# SCH_doorbellv2_2026-01-17.net
KiCad netlist of a schematic drawn in EasyEDA
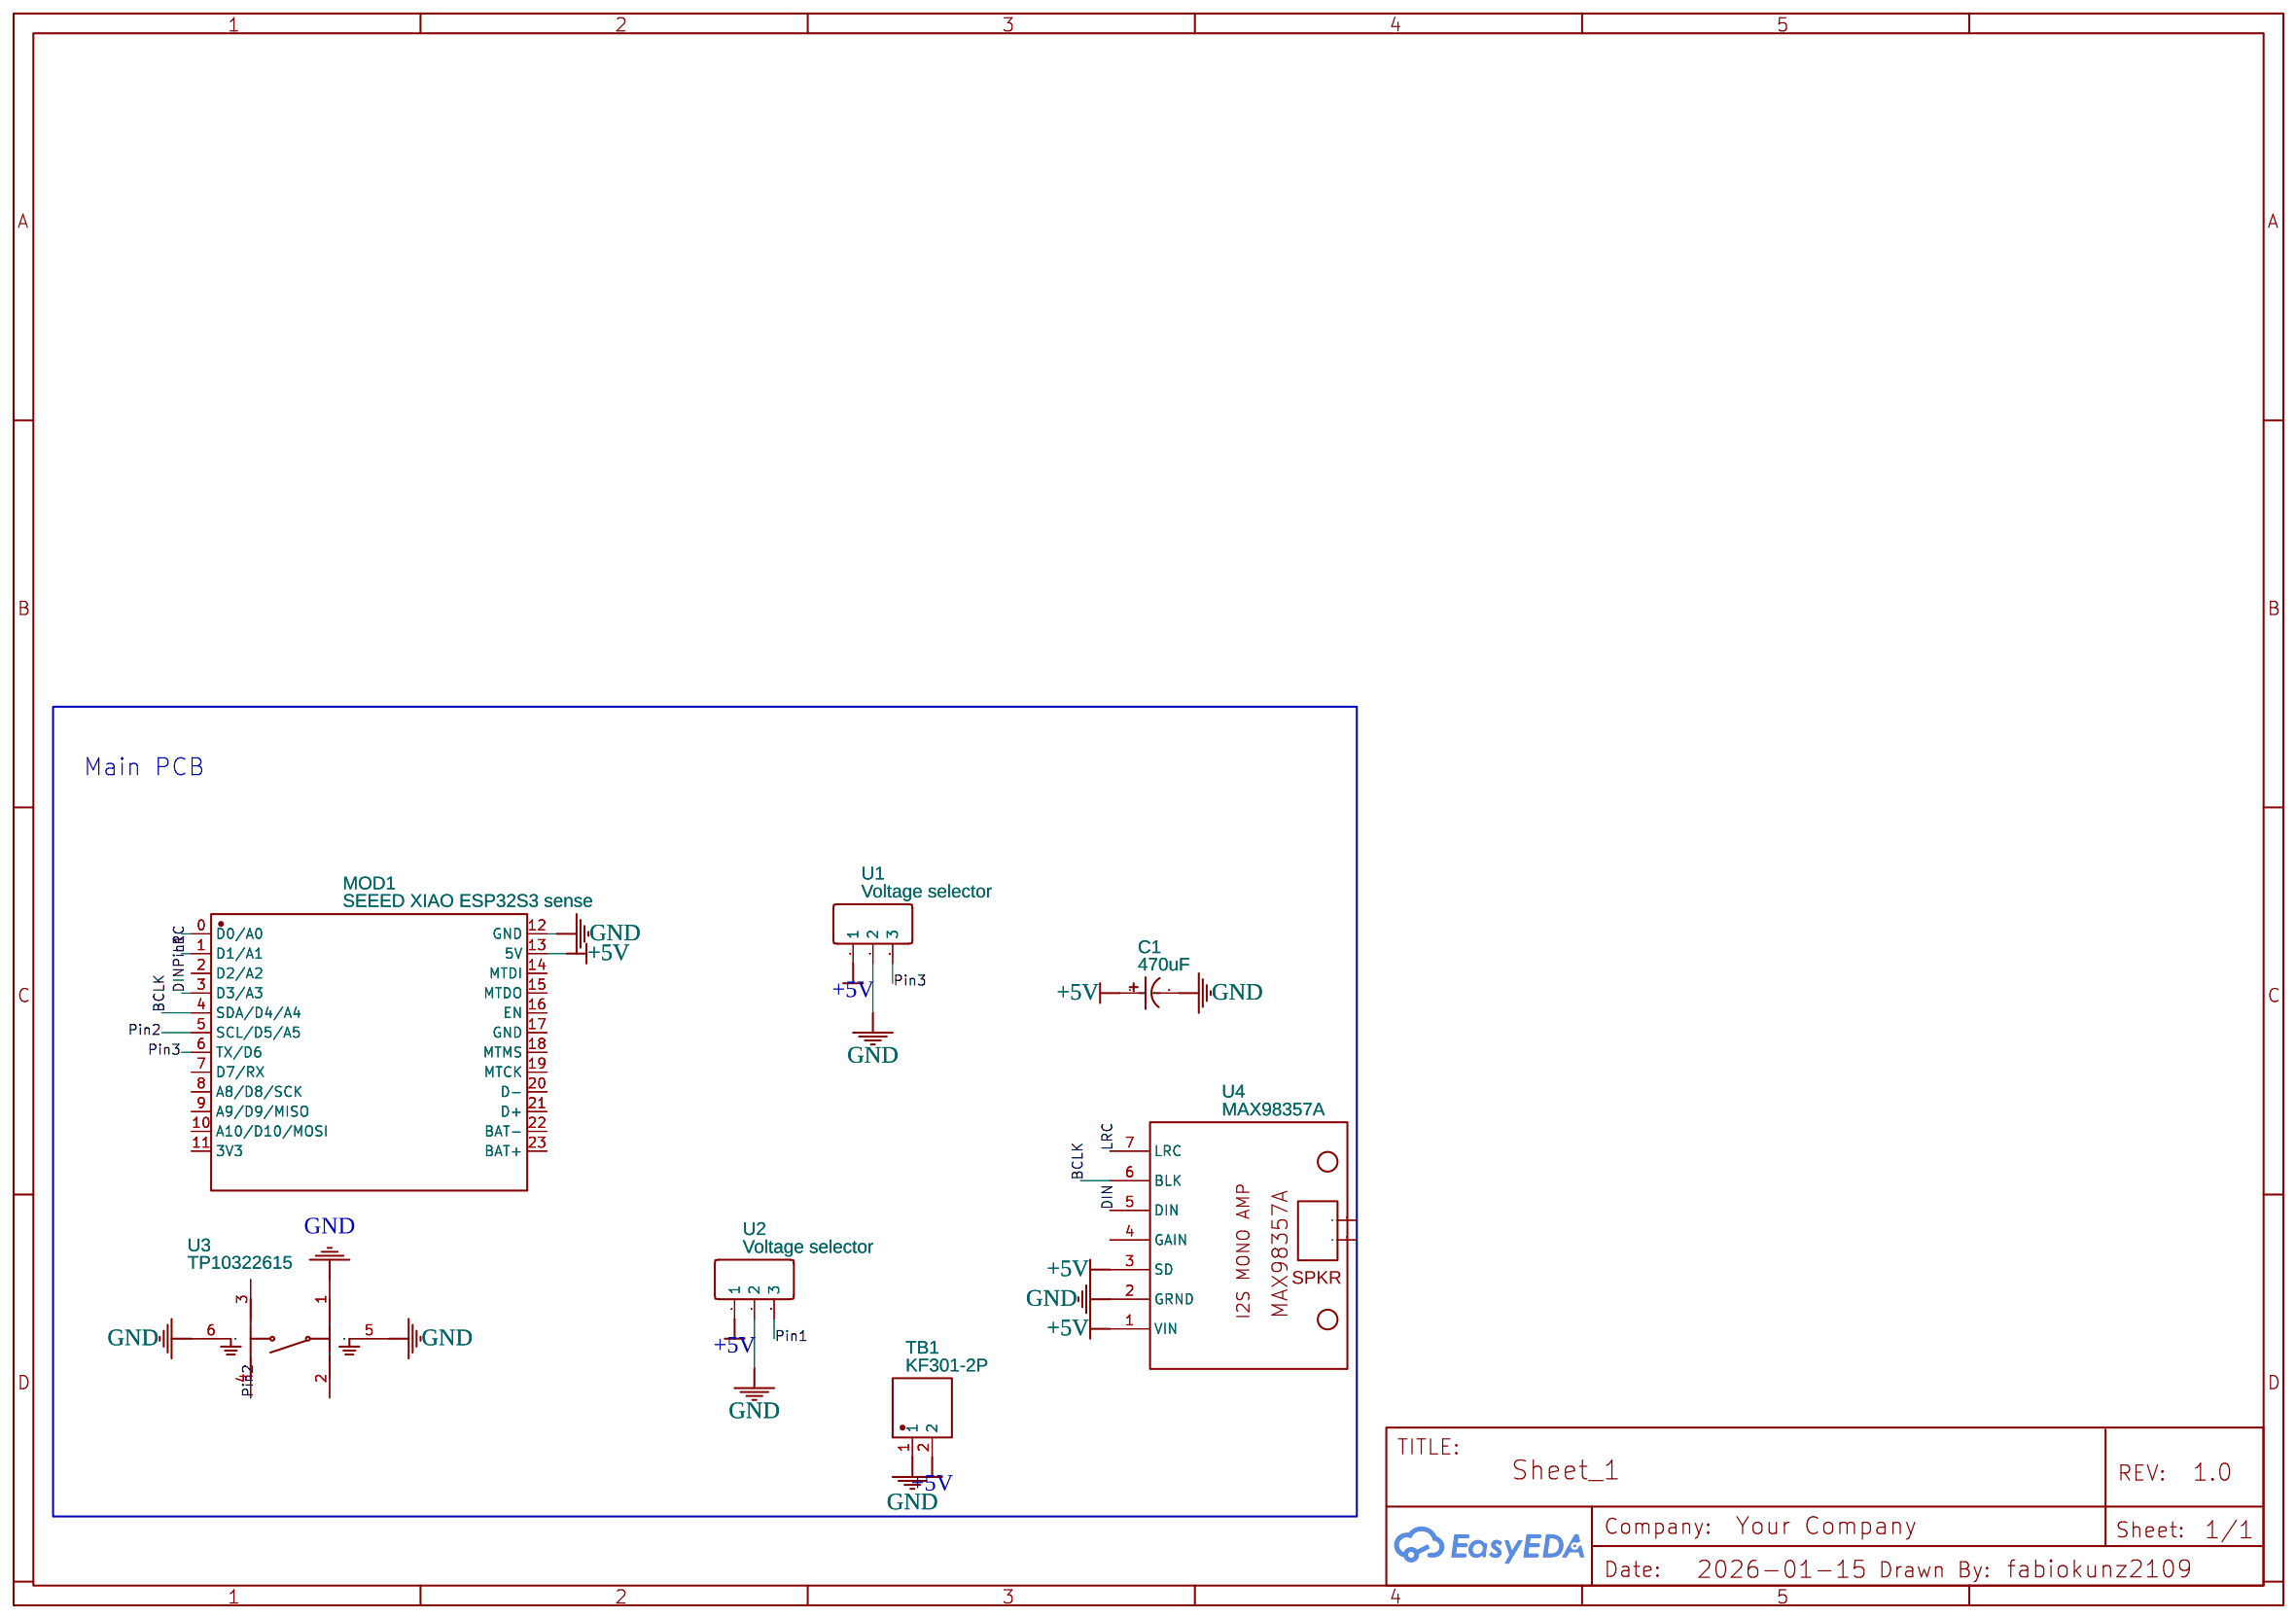
[diagram p0: schematic sheet]

(export (version "E")
  (design (tool "Eeschema 10.0.6"))
  (components
    (comp (ref "C1") (value "470uF") (libsource (lib "") (part "470uF 10V Flat 6.3x12")))
    (comp (ref "MOD1")
      (value "SEEED XIAO ESP32S3 sense")
      (libsource (lib "") (part "SEEED XIAO ESP32S3 sense"))
    )
    (comp (ref "TB1") (value "KF301-2P") (libsource (lib "") (part "KF301-2P")))
    (comp (ref "U1") (value "Voltage selector") (libsource (lib "") (part "Header-Male-2.54-1x3-2-1-Jumper")))
    (comp (ref "U2") (value "Voltage selector") (libsource (lib "") (part "Header-Male-2.54-1x3-2-1-Jumper")))
    (comp (ref "U3")
      (value "TP10322615")
      (fields (field (name "Manufacturer") "ROCPU Switches(台普)"))
      (libsource (lib "") (part "TP10322615"))
    )
    (comp (ref "U4") (value "MAX98357A") (libsource (lib "") (part "MAX98357A COPY")))
  )
  (nets
    (net (code "1") (name "+5V") (class "Default")
      (node (ref "C1") (pin "1") (pinfunction "1_1") (pintype "input"))
      (node (ref "MOD1") (pin "13") (pinfunction "5V_13") (pintype "unspecified"))
      (node (ref "TB1") (pin "2") (pinfunction "2_2") (pintype "unspecified"))
      (node (ref "U1") (pin "1") (pinfunction "1_1") (pintype "unspecified"))
      (node (ref "U2") (pin "1") (pinfunction "1_1") (pintype "unspecified"))
      (node (ref "U4") (pin "1") (pinfunction "VIN_1") (pintype "unspecified"))
      (node (ref "U4") (pin "3") (pinfunction "SD_3") (pintype "unspecified"))
    )
    (net (code "2") (name "/BCLK") (class "Default")
      (node (ref "MOD1") (pin "4") (pinfunction "SDA/D4/A4_4") (pintype "unspecified"))
      (node (ref "U4") (pin "6") (pinfunction "BLK_6") (pintype "unspecified"))
    )
    (net (code "3") (name "/DIN") (class "Default")
      (node (ref "MOD1") (pin "3") (pinfunction "D3/A3_3") (pintype "unspecified"))
      (node (ref "U4") (pin "5") (pinfunction "DIN_5") (pintype "unspecified"))
    )
    (net (code "4") (name "/LRC") (class "Default")
      (node (ref "MOD1") (pin "1") (pinfunction "D1/A1_1") (pintype "unspecified"))
      (node (ref "U4") (pin "7") (pinfunction "LRC_7") (pintype "unspecified"))
    )
    (net (code "5") (name "/Pin1") (class "Default")
      (node (ref "MOD1") (pin "0") (pinfunction "D0/A0_0") (pintype "unspecified"))
      (node (ref "U2") (pin "3") (pinfunction "3_3") (pintype "unspecified"))
    )
    (net (code "6") (name "/Pin2") (class "Default")
      (node (ref "MOD1") (pin "5") (pinfunction "SCL/D5/A5_5") (pintype "unspecified"))
      (node (ref "U3") (pin "4") (pinfunction "4_4") (pintype "unspecified"))
    )
    (net (code "7") (name "/Pin3") (class "Default")
      (node (ref "MOD1") (pin "6") (pinfunction "TX/D6_6") (pintype "unspecified"))
      (node (ref "U1") (pin "3") (pinfunction "3_3") (pintype "unspecified"))
    )
    (net (code "8") (name "GND") (class "Default")
      (node (ref "C1") (pin "2") (pinfunction "2_2") (pintype "input"))
      (node (ref "MOD1") (pin "12") (pinfunction "GND_12") (pintype "unspecified"))
      (node (ref "TB1") (pin "1") (pinfunction "1_1") (pintype "unspecified"))
      (node (ref "U1") (pin "2") (pinfunction "2_2") (pintype "unspecified"))
      (node (ref "U2") (pin "2") (pinfunction "2_2") (pintype "unspecified"))
      (node (ref "U3") (pin "1") (pinfunction "1_1") (pintype "unspecified"))
      (node (ref "U3") (pin "5") (pinfunction "5_5") (pintype "unspecified"))
      (node (ref "U3") (pin "6") (pinfunction "6_6") (pintype "unspecified"))
      (node (ref "U4") (pin "2") (pinfunction "GRND_2") (pintype "unspecified"))
    )
    (net (code "9") (name "unconnected-(MOD1-3V3-Pad11)") (class "Default")
      (node (ref "MOD1") (pin "11") (pinfunction "3V3_11") (pintype "unspecified"))
    )
    (net (code "10") (name "unconnected-(MOD1-A8{slash}D8{slash}SCK-Pad8)") (class "Default")
      (node (ref "MOD1") (pin "8") (pinfunction "A8/D8/SCK_8") (pintype "unspecified"))
    )
    (net (code "11") (name "unconnected-(MOD1-A9{slash}D9{slash}MISO-Pad9)") (class "Default")
      (node (ref "MOD1") (pin "9") (pinfunction "A9/D9/MISO_9") (pintype "unspecified"))
    )
    (net (code "12") (name "unconnected-(MOD1-A10{slash}D10{slash}MOSI-Pad10)") (class "Default")
      (node (ref "MOD1") (pin "10") (pinfunction "A10/D10/MOSI_10") (pintype "unspecified"))
    )
    (net (code "13") (name "unconnected-(MOD1-BAT+-Pad23)") (class "Default")
      (node (ref "MOD1") (pin "23") (pinfunction "BAT+_23") (pintype "unspecified"))
    )
    (net (code "14") (name "unconnected-(MOD1-BAT--Pad22)") (class "Default")
      (node (ref "MOD1") (pin "22") (pinfunction "BAT-_22") (pintype "unspecified"))
    )
    (net (code "15") (name "unconnected-(MOD1-D+-Pad21)") (class "Default")
      (node (ref "MOD1") (pin "21") (pinfunction "D+_21") (pintype "unspecified"))
    )
    (net (code "16") (name "unconnected-(MOD1-D--Pad20)") (class "Default")
      (node (ref "MOD1") (pin "20") (pinfunction "D-_20") (pintype "unspecified"))
    )
    (net (code "17") (name "unconnected-(MOD1-D2{slash}A2-Pad2)") (class "Default")
      (node (ref "MOD1") (pin "2") (pinfunction "D2/A2_2") (pintype "unspecified"))
    )
    (net (code "18") (name "unconnected-(MOD1-D7{slash}RX-Pad7)") (class "Default")
      (node (ref "MOD1") (pin "7") (pinfunction "D7/RX_7") (pintype "unspecified"))
    )
    (net (code "19") (name "unconnected-(MOD1-EN-Pad16)") (class "Default")
      (node (ref "MOD1") (pin "16") (pinfunction "EN_16") (pintype "unspecified"))
    )
    (net (code "20") (name "unconnected-(MOD1-GND-Pad17)") (class "Default")
      (node (ref "MOD1") (pin "17") (pinfunction "GND_17") (pintype "unspecified"))
    )
    (net (code "21") (name "unconnected-(MOD1-MTCK-Pad19)") (class "Default")
      (node (ref "MOD1") (pin "19") (pinfunction "MTCK_19") (pintype "unspecified"))
    )
    (net (code "22") (name "unconnected-(MOD1-MTDI-Pad14)") (class "Default")
      (node (ref "MOD1") (pin "14") (pinfunction "MTDI_14") (pintype "unspecified"))
    )
    (net (code "23") (name "unconnected-(MOD1-MTDO-Pad15)") (class "Default")
      (node (ref "MOD1") (pin "15") (pinfunction "MTDO_15") (pintype "unspecified"))
    )
    (net (code "24") (name "unconnected-(MOD1-MTMS-Pad18)") (class "Default")
      (node (ref "MOD1") (pin "18") (pinfunction "MTMS_18") (pintype "unspecified"))
    )
    (net (code "25") (name "unconnected-(U3-Pad2)") (class "Default")
      (node (ref "U3") (pin "2") (pinfunction "2_2") (pintype "unspecified"))
    )
    (net (code "26") (name "unconnected-(U3-Pad3)") (class "Default")
      (node (ref "U3") (pin "3") (pinfunction "3_3") (pintype "unspecified"))
    )
    (net (code "27") (name "unconnected-(U4-+-Pad1)") (class "Default")
      (node (ref "U4") (pin "1") (pinfunction "+_1") (pintype "unspecified"))
    )
    (net (code "28") (name "unconnected-(U4----Pad2)") (class "Default")
      (node (ref "U4") (pin "2") (pinfunction "--_2") (pintype "unspecified"))
    )
    (net (code "29") (name "unconnected-(U4-GAIN-Pad4)") (class "Default")
      (node (ref "U4") (pin "4") (pinfunction "GAIN_4") (pintype "unspecified"))
    )
  )
)
